# Driver1.net
KiCad netlist of a schematic drawn in Altium Designer
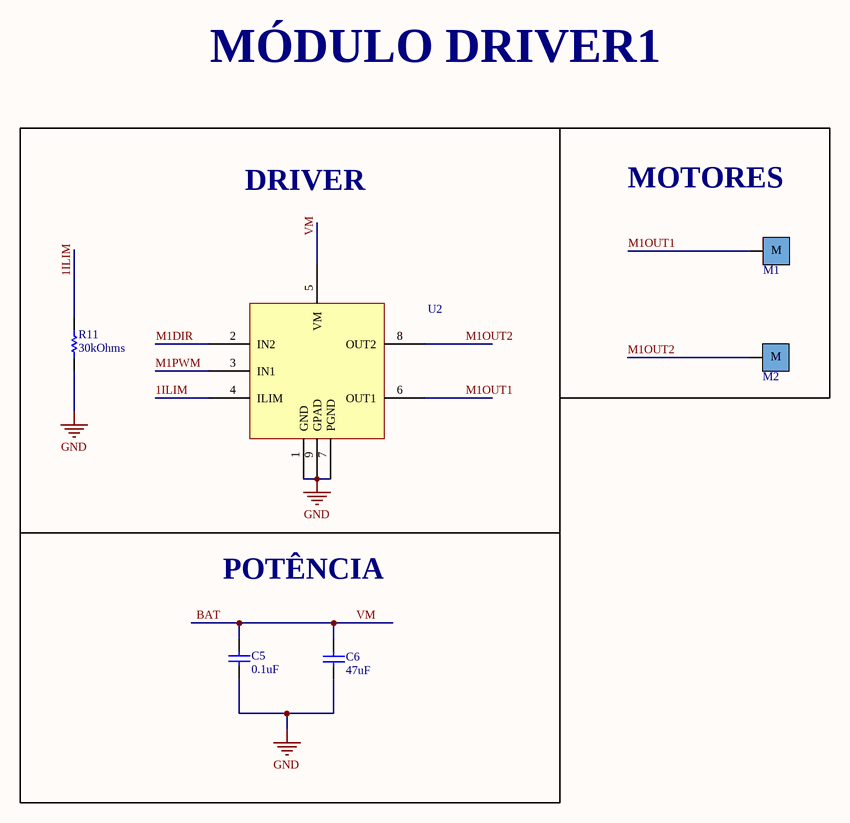
[diagram p0: Driver1.SchDoc]

(export (version "E")
  (design (tool "Eeschema 10.0.6"))
  (components
    (comp (ref "C5")
      (value "0.1uF")
      (footprint "C0805")
      (description "CAP CER 100nF 25V X7R 0805")
      (fields
        (field (name "MANUFACTURER") "Kemet")
        (field (name "PART NUMBER") "C0805C104M3RACTU")
        (field (name "LIBRARY CONTROL - PERSON THAT CHECKED FOOTPRINT") "Cage")
        (field (name "LIBRARY CONTROL - PERSON THAT CHECKED SCHEMATIC") "Cage")
        (field (name "LIBRARY CONTROL - PERSON THAT DID THE LAST UPDATE FOOTPRINT") "Cage")
        (field (name "LIBRARY CONTROL - PERSON THAT DID THE LAST UPDATE SCHEMATIC") "Cage")
      )
      (libsource (lib "Uai!Tecas") (part "C0805C104M3RACTU"))
    )
    (comp (ref "C6")
      (value "47uF")
      (footprint "C1210")
      (description "CAP CER 47uF 16V X6S 1210")
      (fields
        (field (name "MANUFACTURER") "Murata")
        (field (name "PART NUMBER") "GRM32EC81C476KE15K")
        (field (name "LIBRARY CONTROL - PERSON THAT CHECKED FOOTPRINT") "Cage")
        (field (name "LIBRARY CONTROL - PERSON THAT CHECKED SCHEMATIC") "Cage")
        (field (name "LIBRARY CONTROL - PERSON THAT DID THE LAST UPDATE FOOTPRINT") "Prisma")
        (field (name "LIBRARY CONTROL - PERSON THAT DID THE LAST UPDATE SCHEMATIC") "Prisma")
      )
      (libsource (lib "Capacitor") (part "GRM32EC81C476KE15K"))
    )
    (comp (ref "M1")
      (value "Motor Pad")
      (footprint "PAD_MOTOR_MINI")
      (description "MOTOR PAD MINI SUMÔ")
      (libsource (lib "Uai!Tecas") (part "Motor Pad Mini Sumô"))
    )
    (comp (ref "M2")
      (value "Motor Pad")
      (footprint "PAD_MOTOR_MINI")
      (description "MOTOR PAD MINI SUMÔ")
      (libsource (lib "Uai!Tecas") (part "Motor Pad Mini Sumô"))
    )
    (comp (ref "R11")
      (value "30kOhms")
      (footprint "RESC1608X55N")
      (description "RES SMD 30 kOHMS 1% 1/10W 0603")
      (fields
        (field (name "MANUFACTURER") "YAGEO")
        (field (name "PART NUMBER") "RC0603FR-0730KL")
        (field (name "LIBRARY CONTROL - PERSON THAT CHECKED FOOTPRINT") "Guilherme")
        (field (name "LIBRARY CONTROL - PERSON THAT CHECKED SCHEMATIC") "Guilherme")
        (field (name "LIBRARY CONTROL - PERSON THAT DID THE LAST UPDATE FOOTPRINT") "Guilherme")
        (field (name "LIBRARY CONTROL - PERSON THAT DID THE LAST UPDATE SCHEMATIC") "Guilherme")
      )
      (libsource (lib "Uai!Tecas") (part "RC0603FR-0730KL"))
    )
    (comp (ref "U2")
      (value "DRV8871DDA")
      (footprint "SO-PowerPad-8(8_pins)")
      (description "IC MTR DRV (6.5V ~ 45V) (3.5 A) SO-PowerPad-8")
      (fields
        (field (name "MANUFACTURER") "Texas Instruments")
        (field (name "LIBRARY CONTROL - PERSON THAT CHECKED SCHEMATIC") "Stéfany (Ster)")
        (field (name "LIBRARY CONTROL - PERSON THAT CHECKED FOOTPRINT") "Stéfany (Ster)")
        (field (name "LIBRARY CONTROL - PERSON THAT DID THE LAST UPDATE SCHEMATIC") "Stéfany (Ster)")
        (field (name "LIBRARY CONTROL - PERSON THAT DID THE LAST UPDATE FOOTPRINT") "Maria Laura")
      )
      (libsource (lib "Uai!Tecas") (part "DRV8871DDA"))
    )
  )
  (nets
    (net (code "1") (name "/1ILIM") (class "Default")
      (node (ref "R11") (pin "1") (pinfunction "1_1") (pintype "passive"))
      (node (ref "U2") (pin "4") (pinfunction "ILIM_4") (pintype "passive"))
    )
    (net (code "2") (name "/BAT") (class "Default")
      (node (ref "C5") (pin "2") (pinfunction "2_2") (pintype "passive"))
      (node (ref "C6") (pin "2") (pinfunction "2_2") (pintype "passive"))
      (node (ref "U2") (pin "5") (pinfunction "VM_5") (pintype "passive"))
    )
    (net (code "3") (name "/M1DIR") (class "Default")
      (node (ref "U2") (pin "2") (pinfunction "IN2_2") (pintype "passive"))
    )
    (net (code "4") (name "/M1OUT1") (class "Default")
      (node (ref "M1") (pin "M") (pinfunction "M_M") (pintype "passive"))
      (node (ref "U2") (pin "6") (pinfunction "OUT1_6") (pintype "passive"))
    )
    (net (code "5") (name "/M1OUT2") (class "Default")
      (node (ref "M2") (pin "M") (pinfunction "M_M") (pintype "passive"))
      (node (ref "U2") (pin "8") (pinfunction "OUT2_8") (pintype "passive"))
    )
    (net (code "6") (name "/M1PWM") (class "Default")
      (node (ref "U2") (pin "3") (pinfunction "IN1_3") (pintype "passive"))
    )
    (net (code "7") (name "GND") (class "Default")
      (node (ref "C5") (pin "1") (pinfunction "1_1") (pintype "passive"))
      (node (ref "C6") (pin "1") (pinfunction "1_1") (pintype "passive"))
      (node (ref "R11") (pin "2") (pinfunction "2_2") (pintype "passive"))
      (node (ref "U2") (pin "1") (pinfunction "GND_1") (pintype "passive"))
      (node (ref "U2") (pin "7") (pinfunction "PGND_7") (pintype "passive"))
      (node (ref "U2") (pin "9") (pinfunction "GPAD_9") (pintype "passive"))
    )
  )
)
